# nodemcu1.net
KiCad netlist of a schematic drawn in EAGLE
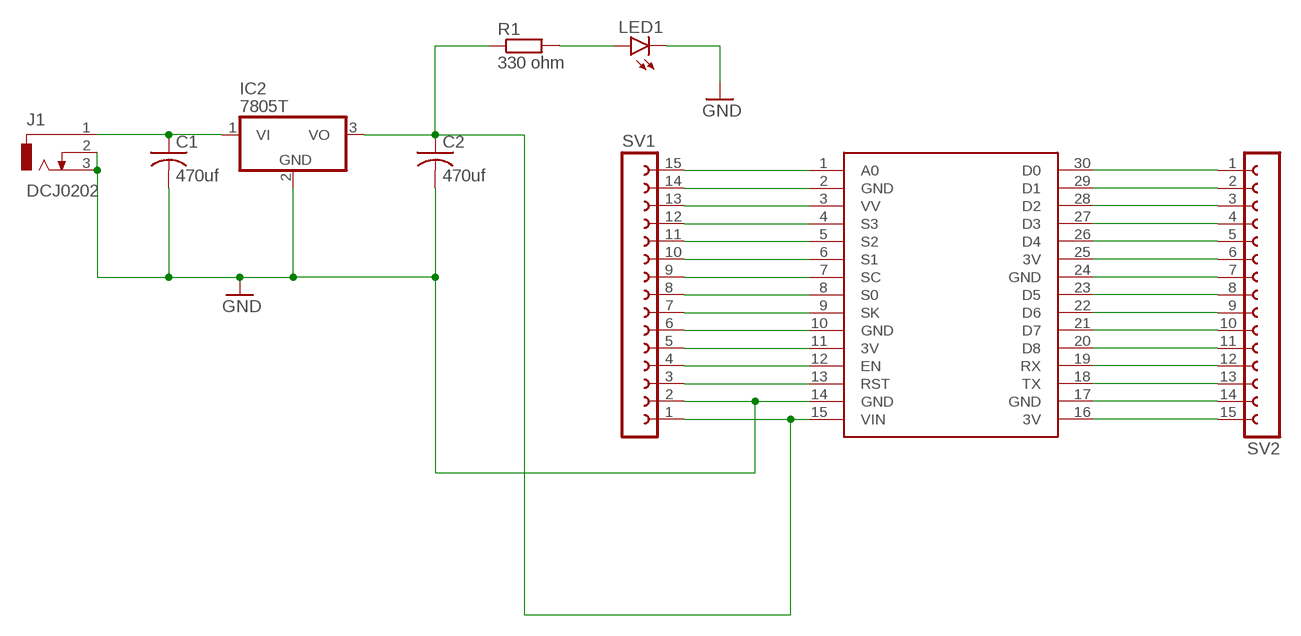
[diagram p0: schematic, sheet 1]

(export (version "E")
  (design (tool "Eeschema 10.0.6"))
  (components
    (comp (ref "C1")
      (value "470uf")
      (footprint "eagle-import:C025-024X044")
      (libsource (lib "eagle-import") (part "C-US025-024X044"))
    )
    (comp (ref "C2")
      (value "470uf")
      (footprint "eagle-import:C025-024X044")
      (libsource (lib "eagle-import") (part "C-US025-024X044"))
    )
    (comp (ref "IC2")
      (value "7805T")
      (footprint "eagle-import:TO220H")
      (libsource (lib "eagle-import") (part "78T05"))
    )
    (comp (ref "J1")
      (value "DCJ0202")
      (footprint "eagle-import:DCJ0202")
      (libsource (lib "eagle-import") (part "DCJ0202"))
    )
    (comp (ref "LED1")
      (value "LEDLD260")
      (footprint "eagle-import:LD260")
      (libsource (lib "eagle-import") (part "LEDLD260"))
    )
    (comp (ref "R1")
      (value "330 ohm")
      (footprint "eagle-import:0204_5")
      (libsource (lib "eagle-import") (part "R-EU_0204/5"))
    )
    (comp (ref "SV1")
      (value "FE15-1")
      (footprint "eagle-import:FE15")
      (libsource (lib "eagle-import") (part "FE15-1"))
    )
    (comp (ref "SV2")
      (value "FE15-1")
      (footprint "eagle-import:FE15")
      (libsource (lib "eagle-import") (part "FE15-1"))
    )
    (comp (ref "U$1")
      (value "NODEMCU")
      (footprint "eagle-import:NODEMCU")
      (libsource (lib "eagle-import") (part "NODEMCU"))
    )
  )
  (nets
    (net (code "1") (name "GND") (class "Default")
      (node (ref "C1") (pin "2") (pinfunction "2_2") (pintype "passive"))
      (node (ref "C2") (pin "2") (pinfunction "2_2") (pintype "passive"))
      (node (ref "IC2") (pin "2") (pinfunction "GND_2") (pintype "passive"))
      (node (ref "J1") (pin "2") (pinfunction "2_2") (pintype "passive"))
      (node (ref "J1") (pin "3") (pinfunction "3_3") (pintype "passive"))
      (node (ref "LED1") (pin "K") (pinfunction "C_K") (pintype "passive"))
      (node (ref "SV1") (pin "2") (pinfunction "2_2") (pintype "passive"))
      (node (ref "U$1") (pin "14") (pinfunction "GND_14") (pintype "power_in"))
    )
    (net (code "2") (name "Net-(IC2-VI)") (class "Default")
      (node (ref "C1") (pin "1") (pinfunction "1_1") (pintype "passive"))
      (node (ref "IC2") (pin "1") (pinfunction "VI_1") (pintype "input"))
      (node (ref "J1") (pin "1") (pinfunction "1_1") (pintype "passive"))
    )
    (net (code "3") (name "Net-(IC2-VO)") (class "Default")
      (node (ref "C2") (pin "1") (pinfunction "1_1") (pintype "passive"))
      (node (ref "IC2") (pin "3") (pinfunction "VO_3") (pintype "passive"))
      (node (ref "R1") (pin "1") (pinfunction "1_1") (pintype "passive"))
      (node (ref "SV1") (pin "1") (pinfunction "1_1") (pintype "passive"))
      (node (ref "U$1") (pin "15") (pinfunction "VIN_15") (pintype "bidirectional"))
    )
    (net (code "4") (name "Net-(LED1-PadA)") (class "Default")
      (node (ref "LED1") (pin "A") (pinfunction "A_A") (pintype "passive"))
      (node (ref "R1") (pin "2") (pinfunction "2_2") (pintype "passive"))
    )
    (net (code "5") (name "Net-(SV1-Pad5)") (class "Default")
      (node (ref "SV1") (pin "5") (pinfunction "5_5") (pintype "passive"))
      (node (ref "U$1") (pin "11") (pinfunction "3V_11") (pintype "power_in"))
    )
    (net (code "6") (name "Net-(SV1-Pad6)") (class "Default")
      (node (ref "SV1") (pin "6") (pinfunction "6_6") (pintype "passive"))
      (node (ref "U$1") (pin "10") (pinfunction "GND_10") (pintype "power_in"))
    )
    (net (code "7") (name "Net-(SV1-Pad14)") (class "Default")
      (node (ref "SV1") (pin "14") (pinfunction "14_14") (pintype "passive"))
      (node (ref "U$1") (pin "2") (pinfunction "GND_2") (pintype "power_in"))
    )
    (net (code "8") (name "Net-(SV2-Pad6)") (class "Default")
      (node (ref "SV2") (pin "6") (pinfunction "6_6") (pintype "passive"))
      (node (ref "U$1") (pin "25") (pinfunction "3V_25") (pintype "power_in"))
    )
    (net (code "9") (name "Net-(SV2-Pad7)") (class "Default")
      (node (ref "SV2") (pin "7") (pinfunction "7_7") (pintype "passive"))
      (node (ref "U$1") (pin "24") (pinfunction "GND_24") (pintype "power_in"))
    )
    (net (code "10") (name "Net-(SV2-Pad14)") (class "Default")
      (node (ref "SV2") (pin "14") (pinfunction "14_14") (pintype "passive"))
      (node (ref "U$1") (pin "17") (pinfunction "GND_17") (pintype "power_in"))
    )
    (net (code "11") (name "Net-(SV2-Pad15)") (class "Default")
      (node (ref "SV2") (pin "15") (pinfunction "15_15") (pintype "passive"))
      (node (ref "U$1") (pin "16") (pinfunction "3V_16") (pintype "power_in"))
    )
    (net (code "12") (name "Net-(U$1-A0)") (class "Default")
      (node (ref "SV1") (pin "15") (pinfunction "15_15") (pintype "passive"))
      (node (ref "U$1") (pin "1") (pinfunction "A0_1") (pintype "bidirectional"))
    )
    (net (code "13") (name "Net-(U$1-D0)") (class "Default")
      (node (ref "SV2") (pin "1") (pinfunction "1_1") (pintype "passive"))
      (node (ref "U$1") (pin "30") (pinfunction "D0_30") (pintype "bidirectional"))
    )
    (net (code "14") (name "Net-(U$1-D1)") (class "Default")
      (node (ref "SV2") (pin "2") (pinfunction "2_2") (pintype "passive"))
      (node (ref "U$1") (pin "29") (pinfunction "D1_29") (pintype "bidirectional"))
    )
    (net (code "15") (name "Net-(U$1-D2)") (class "Default")
      (node (ref "SV2") (pin "3") (pinfunction "3_3") (pintype "passive"))
      (node (ref "U$1") (pin "28") (pinfunction "D2_28") (pintype "bidirectional"))
    )
    (net (code "16") (name "Net-(U$1-D3)") (class "Default")
      (node (ref "SV2") (pin "4") (pinfunction "4_4") (pintype "passive"))
      (node (ref "U$1") (pin "27") (pinfunction "D3_27") (pintype "bidirectional"))
    )
    (net (code "17") (name "Net-(U$1-D4)") (class "Default")
      (node (ref "SV2") (pin "5") (pinfunction "5_5") (pintype "passive"))
      (node (ref "U$1") (pin "26") (pinfunction "D4_26") (pintype "bidirectional"))
    )
    (net (code "18") (name "Net-(U$1-D5)") (class "Default")
      (node (ref "SV2") (pin "8") (pinfunction "8_8") (pintype "passive"))
      (node (ref "U$1") (pin "23") (pinfunction "D5_23") (pintype "bidirectional"))
    )
    (net (code "19") (name "Net-(U$1-D6)") (class "Default")
      (node (ref "SV2") (pin "9") (pinfunction "9_9") (pintype "passive"))
      (node (ref "U$1") (pin "22") (pinfunction "D6_22") (pintype "bidirectional"))
    )
    (net (code "20") (name "Net-(U$1-D7)") (class "Default")
      (node (ref "SV2") (pin "10") (pinfunction "10_10") (pintype "passive"))
      (node (ref "U$1") (pin "21") (pinfunction "D7_21") (pintype "bidirectional"))
    )
    (net (code "21") (name "Net-(U$1-D8)") (class "Default")
      (node (ref "SV2") (pin "11") (pinfunction "11_11") (pintype "passive"))
      (node (ref "U$1") (pin "20") (pinfunction "D8_20") (pintype "bidirectional"))
    )
    (net (code "22") (name "Net-(U$1-EN)") (class "Default")
      (node (ref "SV1") (pin "4") (pinfunction "4_4") (pintype "passive"))
      (node (ref "U$1") (pin "12") (pinfunction "EN_12") (pintype "bidirectional"))
    )
    (net (code "23") (name "Net-(U$1-RST)") (class "Default")
      (node (ref "SV1") (pin "3") (pinfunction "3_3") (pintype "passive"))
      (node (ref "U$1") (pin "13") (pinfunction "RST_13") (pintype "bidirectional"))
    )
    (net (code "24") (name "Net-(U$1-RX)") (class "Default")
      (node (ref "SV2") (pin "12") (pinfunction "12_12") (pintype "passive"))
      (node (ref "U$1") (pin "19") (pinfunction "RX_19") (pintype "bidirectional"))
    )
    (net (code "25") (name "Net-(U$1-S0)") (class "Default")
      (node (ref "SV1") (pin "8") (pinfunction "8_8") (pintype "passive"))
      (node (ref "U$1") (pin "8") (pinfunction "S0_8") (pintype "bidirectional"))
    )
    (net (code "26") (name "Net-(U$1-S1)") (class "Default")
      (node (ref "SV1") (pin "10") (pinfunction "10_10") (pintype "passive"))
      (node (ref "U$1") (pin "6") (pinfunction "S1_6") (pintype "bidirectional"))
    )
    (net (code "27") (name "Net-(U$1-S2)") (class "Default")
      (node (ref "SV1") (pin "11") (pinfunction "11_11") (pintype "passive"))
      (node (ref "U$1") (pin "5") (pinfunction "S2_5") (pintype "bidirectional"))
    )
    (net (code "28") (name "Net-(U$1-S3)") (class "Default")
      (node (ref "SV1") (pin "12") (pinfunction "12_12") (pintype "passive"))
      (node (ref "U$1") (pin "4") (pinfunction "S3_4") (pintype "bidirectional"))
    )
    (net (code "29") (name "Net-(U$1-SC)") (class "Default")
      (node (ref "SV1") (pin "9") (pinfunction "9_9") (pintype "passive"))
      (node (ref "U$1") (pin "7") (pinfunction "SC_7") (pintype "bidirectional"))
    )
    (net (code "30") (name "Net-(U$1-SK)") (class "Default")
      (node (ref "SV1") (pin "7") (pinfunction "7_7") (pintype "passive"))
      (node (ref "U$1") (pin "9") (pinfunction "SK_9") (pintype "bidirectional"))
    )
    (net (code "31") (name "Net-(U$1-TX)") (class "Default")
      (node (ref "SV2") (pin "13") (pinfunction "13_13") (pintype "passive"))
      (node (ref "U$1") (pin "18") (pinfunction "TX_18") (pintype "bidirectional"))
    )
    (net (code "32") (name "Net-(U$1-VV)") (class "Default")
      (node (ref "SV1") (pin "13") (pinfunction "13_13") (pintype "passive"))
      (node (ref "U$1") (pin "3") (pinfunction "VV_3") (pintype "bidirectional"))
    )
  )
)
